# legatus_0_1.net
KiCad netlist of a schematic drawn in EAGLE
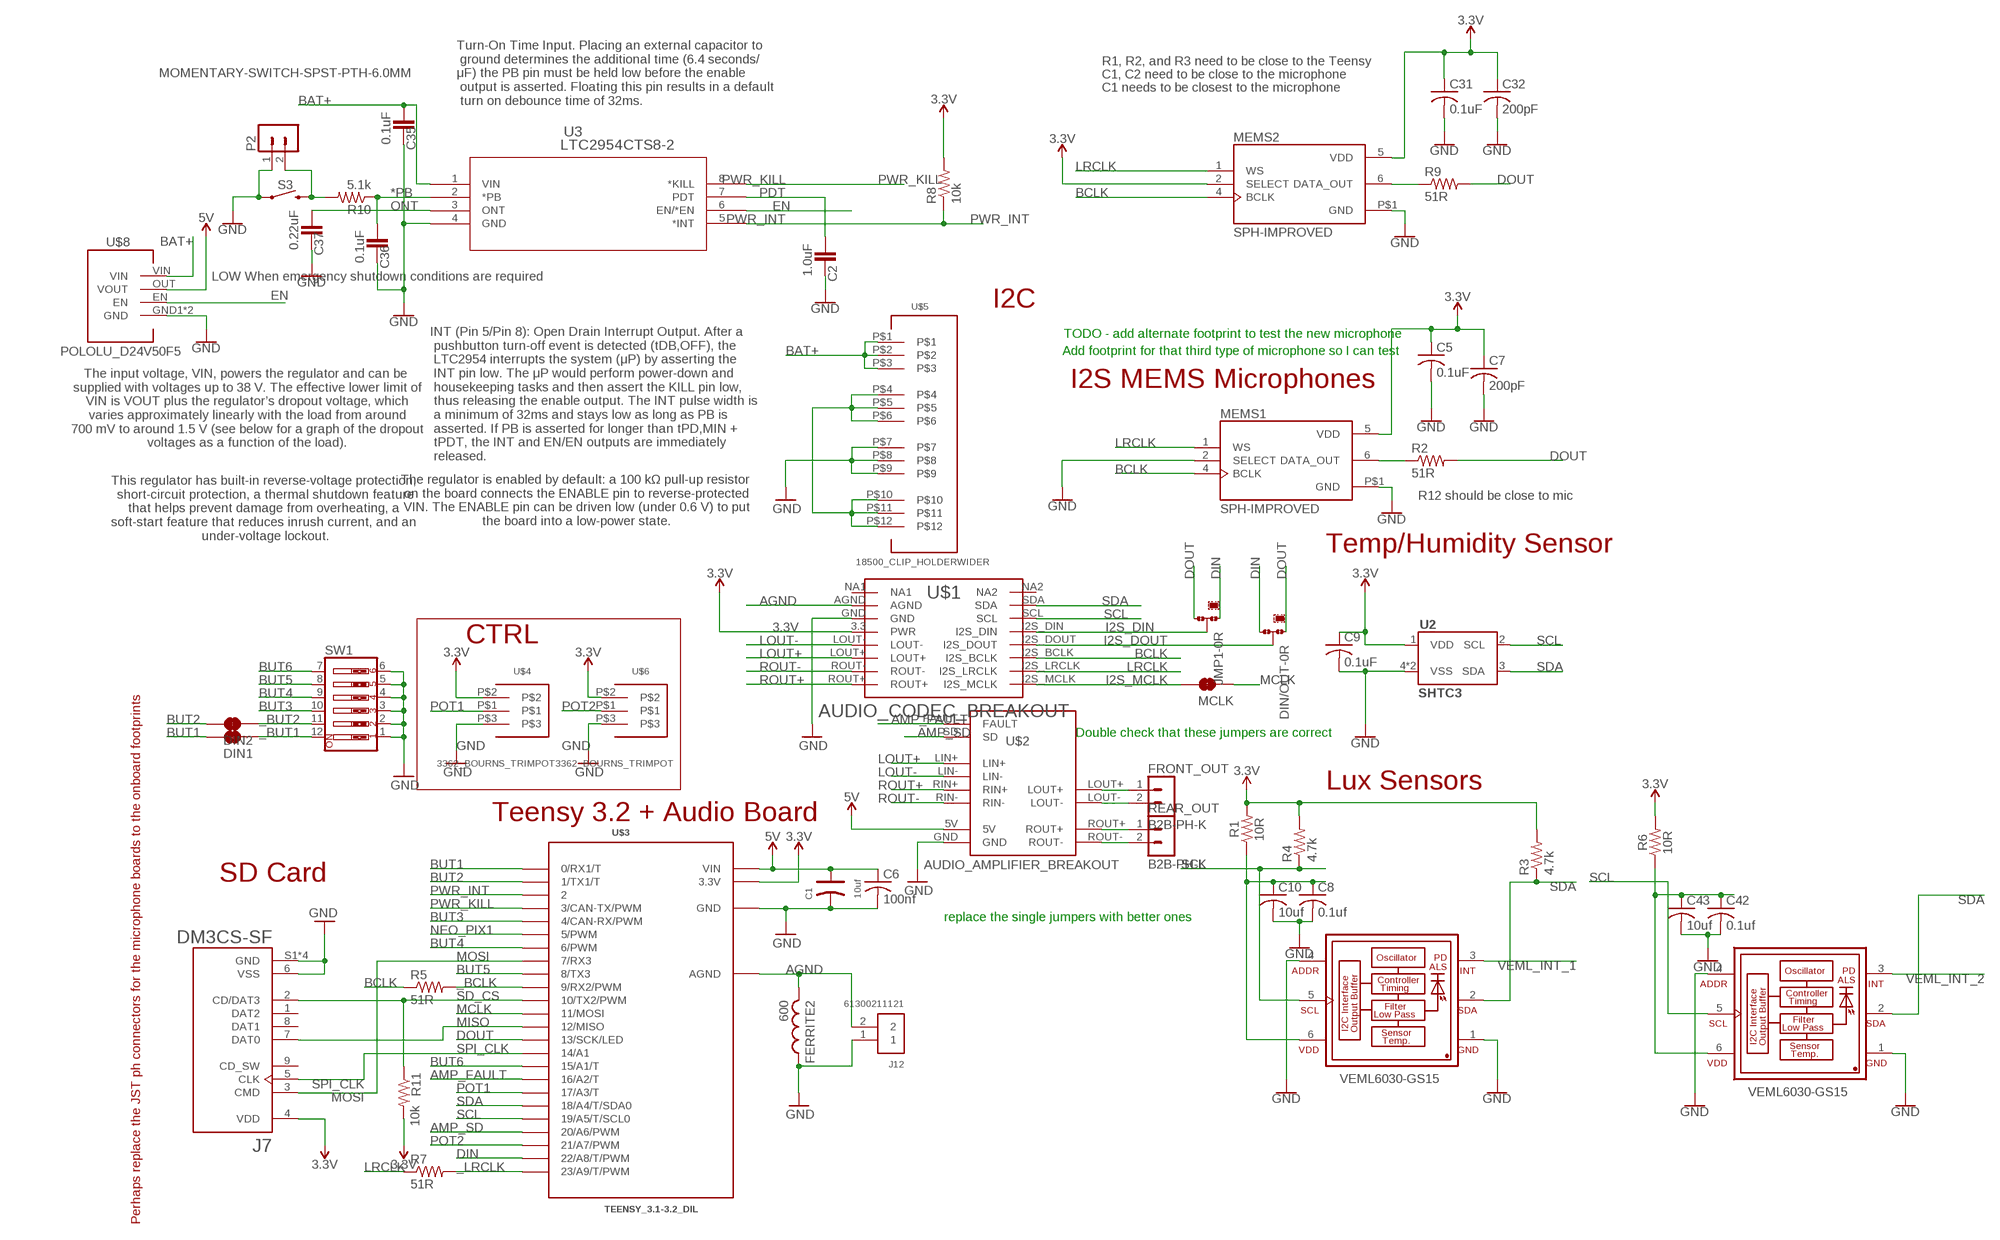
[diagram p0: schematic, sheet 1]
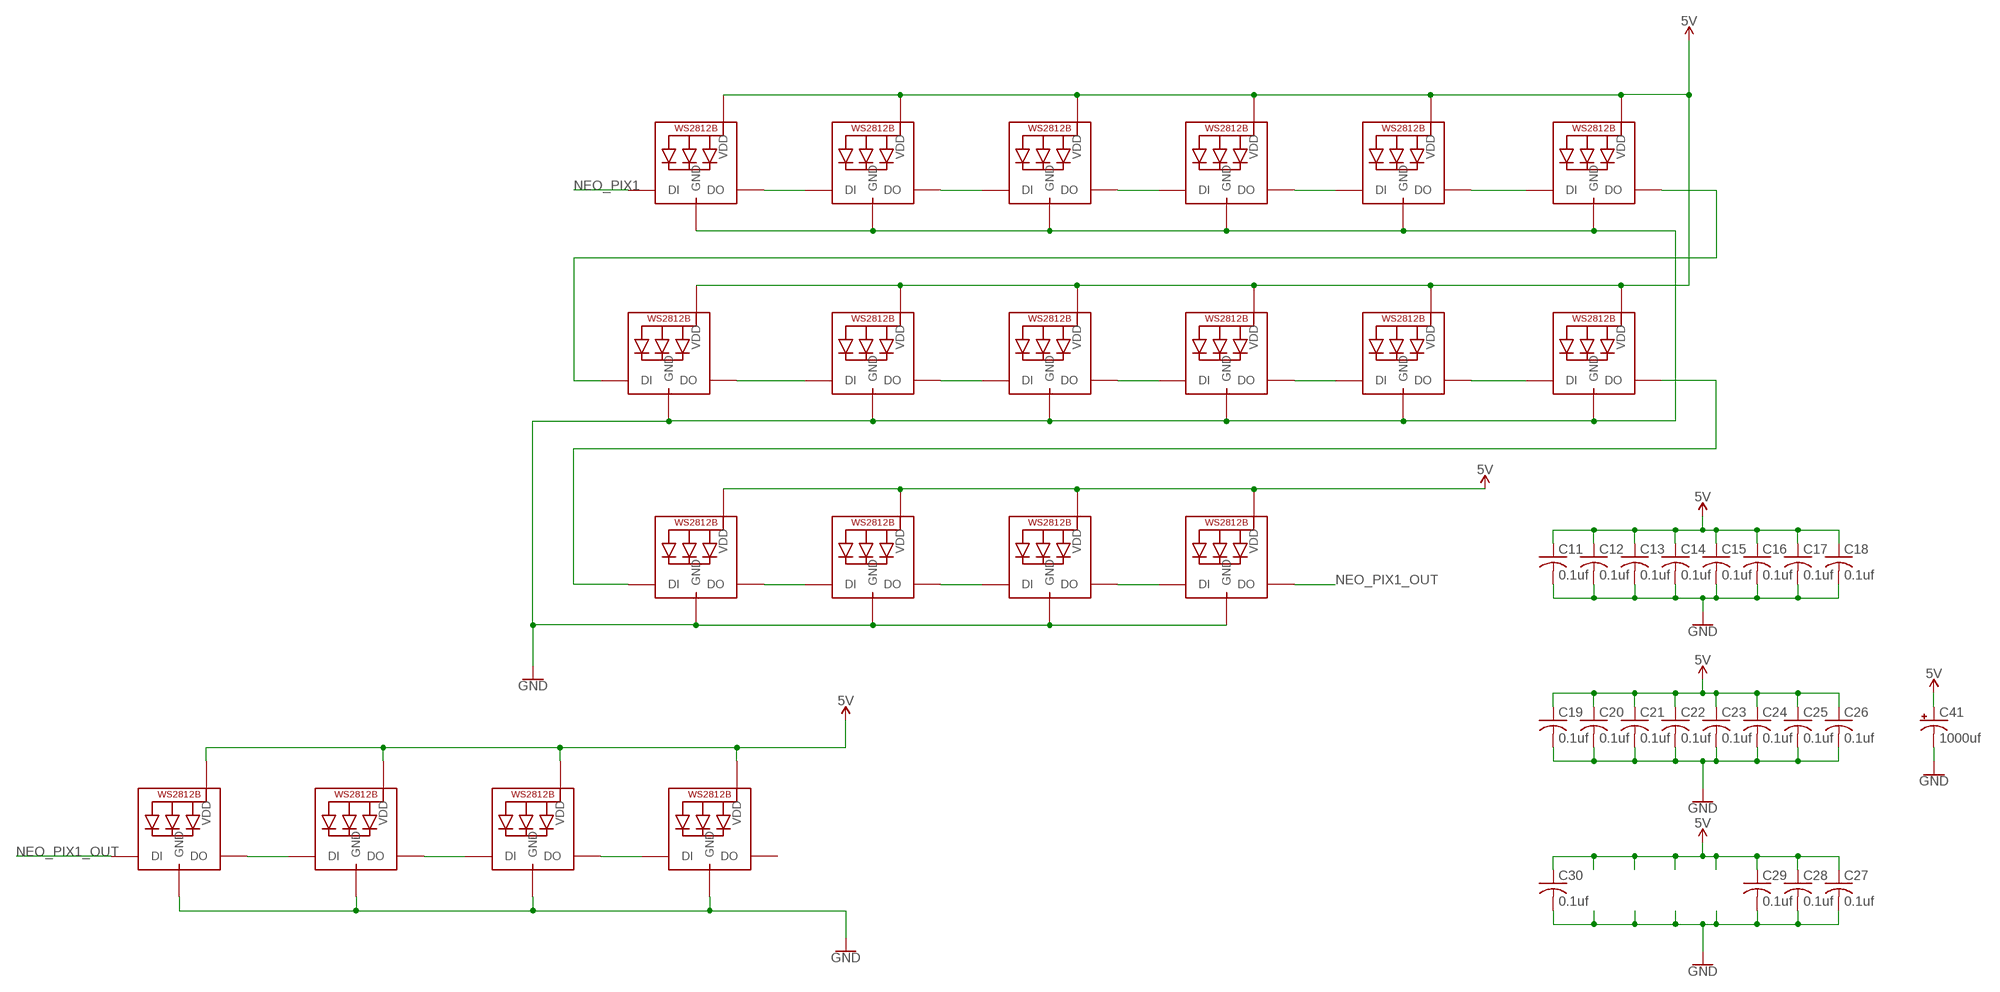
[diagram p1: schematic, sheet 2]

(export (version "E")
  (design (tool "Eeschema 10.0.6"))
  (components
    (comp (ref "C11")
      (value "0.1uf")
      (footprint "eagle-import:C0805")
      (libsource (lib "eagle-import") (part "rcl_334_C-USC0805"))
    )
    (comp (ref "C12")
      (value "0.1uf")
      (footprint "eagle-import:C0805")
      (libsource (lib "eagle-import") (part "rcl_334_C-USC0805"))
    )
    (comp (ref "C13")
      (value "0.1uf")
      (footprint "eagle-import:C0805")
      (libsource (lib "eagle-import") (part "rcl_334_C-USC0805"))
    )
    (comp (ref "C14")
      (value "0.1uf")
      (footprint "eagle-import:C0805")
      (libsource (lib "eagle-import") (part "rcl_334_C-USC0805"))
    )
    (comp (ref "C15")
      (value "0.1uf")
      (footprint "eagle-import:C0805")
      (libsource (lib "eagle-import") (part "rcl_334_C-USC0805"))
    )
    (comp (ref "C16")
      (value "0.1uf")
      (footprint "eagle-import:C0805")
      (libsource (lib "eagle-import") (part "rcl_334_C-USC0805"))
    )
    (comp (ref "C17")
      (value "0.1uf")
      (footprint "eagle-import:C0805")
      (libsource (lib "eagle-import") (part "rcl_334_C-USC0805"))
    )
    (comp (ref "C18")
      (value "0.1uf")
      (footprint "eagle-import:C0805")
      (libsource (lib "eagle-import") (part "rcl_334_C-USC0805"))
    )
    (comp (ref "C19")
      (value "0.1uf")
      (footprint "eagle-import:C0805")
      (libsource (lib "eagle-import") (part "rcl_334_C-USC0805"))
    )
    (comp (ref "C20")
      (value "0.1uf")
      (footprint "eagle-import:C0805")
      (libsource (lib "eagle-import") (part "rcl_334_C-USC0805"))
    )
    (comp (ref "C21")
      (value "0.1uf")
      (footprint "eagle-import:C0805")
      (libsource (lib "eagle-import") (part "rcl_334_C-USC0805"))
    )
    (comp (ref "C22")
      (value "0.1uf")
      (footprint "eagle-import:C0805")
      (libsource (lib "eagle-import") (part "rcl_334_C-USC0805"))
    )
    (comp (ref "C23")
      (value "0.1uf")
      (footprint "eagle-import:C0805")
      (libsource (lib "eagle-import") (part "rcl_334_C-USC0805"))
    )
    (comp (ref "C24")
      (value "0.1uf")
      (footprint "eagle-import:C0805")
      (libsource (lib "eagle-import") (part "rcl_334_C-USC0805"))
    )
    (comp (ref "C25")
      (value "0.1uf")
      (footprint "eagle-import:C0805")
      (libsource (lib "eagle-import") (part "rcl_334_C-USC0805"))
    )
    (comp (ref "C26")
      (value "0.1uf")
      (footprint "eagle-import:C0805")
      (libsource (lib "eagle-import") (part "rcl_334_C-USC0805"))
    )
    (comp (ref "C27")
      (value "0.1uf")
      (footprint "eagle-import:C0805")
      (libsource (lib "eagle-import") (part "rcl_334_C-USC0805"))
    )
    (comp (ref "C28")
      (value "0.1uf")
      (footprint "eagle-import:C0805")
      (libsource (lib "eagle-import") (part "rcl_334_C-USC0805"))
    )
    (comp (ref "C29")
      (value "0.1uf")
      (footprint "eagle-import:C0805")
      (libsource (lib "eagle-import") (part "rcl_334_C-USC0805"))
    )
    (comp (ref "C30")
      (value "0.1uf")
      (footprint "eagle-import:C0805")
      (libsource (lib "eagle-import") (part "rcl_334_C-USC0805"))
    )
    (comp (ref "C41")
      (value "1000uf")
      (footprint "eagle-import:153CLV-1010")
      (libsource (lib "eagle-import") (part "CPOL-US153CLV-1010"))
    )
    (comp (ref "LED1")
      (value "WS2812B_5050N")
      (footprint "eagle-import:WS2812B-NARROW")
      (libsource (lib "eagle-import") (part "WS2812B_5050N"))
    )
    (comp (ref "LED2")
      (value "WS2812B_5050N")
      (footprint "eagle-import:WS2812B-NARROW")
      (libsource (lib "eagle-import") (part "WS2812B_5050N"))
    )
    (comp (ref "LED3")
      (value "WS2812B_5050N")
      (footprint "eagle-import:WS2812B-NARROW")
      (libsource (lib "eagle-import") (part "WS2812B_5050N"))
    )
    (comp (ref "LED4")
      (value "WS2812B_5050N")
      (footprint "eagle-import:WS2812B-NARROW")
      (libsource (lib "eagle-import") (part "WS2812B_5050N"))
    )
    (comp (ref "LED5")
      (value "WS2812B_5050N")
      (footprint "eagle-import:WS2812B-NARROW")
      (libsource (lib "eagle-import") (part "WS2812B_5050N"))
    )
    (comp (ref "LED6")
      (value "WS2812B_5050N")
      (footprint "eagle-import:WS2812B-NARROW")
      (libsource (lib "eagle-import") (part "WS2812B_5050N"))
    )
    (comp (ref "LED7")
      (value "WS2812B_5050N")
      (footprint "eagle-import:WS2812B-NARROW")
      (libsource (lib "eagle-import") (part "WS2812B_5050N"))
    )
    (comp (ref "LED8")
      (value "WS2812B_5050N")
      (footprint "eagle-import:WS2812B-NARROW")
      (libsource (lib "eagle-import") (part "WS2812B_5050N"))
    )
    (comp (ref "LED9")
      (value "WS2812B_5050N")
      (footprint "eagle-import:WS2812B-NARROW")
      (libsource (lib "eagle-import") (part "WS2812B_5050N"))
    )
    (comp (ref "LED10")
      (value "WS2812B_5050N")
      (footprint "eagle-import:WS2812B-NARROW")
      (libsource (lib "eagle-import") (part "WS2812B_5050N"))
    )
    (comp (ref "LED11")
      (value "WS2812B_5050N")
      (footprint "eagle-import:WS2812B-NARROW")
      (libsource (lib "eagle-import") (part "WS2812B_5050N"))
    )
    (comp (ref "LED12")
      (value "WS2812B_5050N")
      (footprint "eagle-import:WS2812B-NARROW")
      (libsource (lib "eagle-import") (part "WS2812B_5050N"))
    )
    (comp (ref "LED13")
      (value "WS2812B_5050N")
      (footprint "eagle-import:WS2812B-NARROW")
      (libsource (lib "eagle-import") (part "WS2812B_5050N"))
    )
    (comp (ref "LED14")
      (value "WS2812B_5050N")
      (footprint "eagle-import:WS2812B-NARROW")
      (libsource (lib "eagle-import") (part "WS2812B_5050N"))
    )
    (comp (ref "LED15")
      (value "WS2812B_5050N")
      (footprint "eagle-import:WS2812B-NARROW")
      (libsource (lib "eagle-import") (part "WS2812B_5050N"))
    )
    (comp (ref "LED16")
      (value "WS2812B_5050N")
      (footprint "eagle-import:WS2812B-NARROW")
      (libsource (lib "eagle-import") (part "WS2812B_5050N"))
    )
    (comp (ref "LED17")
      (value "WS2812B_5050N")
      (footprint "eagle-import:WS2812B-NARROW")
      (libsource (lib "eagle-import") (part "WS2812B_5050N"))
    )
    (comp (ref "LED18")
      (value "WS2812B_5050N")
      (footprint "eagle-import:WS2812B-NARROW")
      (libsource (lib "eagle-import") (part "WS2812B_5050N"))
    )
    (comp (ref "LED19")
      (value "WS2812B_5050N")
      (footprint "eagle-import:WS2812B-NARROW")
      (libsource (lib "eagle-import") (part "WS2812B_5050N"))
    )
    (comp (ref "LED20")
      (value "WS2812B_5050N")
      (footprint "eagle-import:WS2812B-NARROW")
      (libsource (lib "eagle-import") (part "WS2812B_5050N"))
    )
    (comp (ref "C1")
      (value "10uf")
      (footprint "eagle-import:PC-D5.3MM")
      (fields (field (name "MPN") "KS 100uF/16V"))
      (libsource (lib "eagle-import") (part "DIP-ALUMINUM-47UF-16V(D5-H7MM)"))
    )
    (comp (ref "C2")
      (value "1.0uF")
      (footprint "eagle-import:CAPC2012X110")
      (libsource (lib "eagle-import") (part "CCHIP-0805(2012-METRIC)_"))
    )
    (comp (ref "C5")
      (value "0.1uF")
      (footprint "eagle-import:C0805")
      (libsource (lib "eagle-import") (part "rcl_334_C-USC0805"))
    )
    (comp (ref "C6")
      (value "100nf")
      (footprint "eagle-import:C2012")
      (libsource (lib "eagle-import") (part "C-USC2012"))
    )
    (comp (ref "C7")
      (value "200pF")
      (footprint "eagle-import:C0805")
      (libsource (lib "eagle-import") (part "rcl_334_C-USC0805"))
    )
    (comp (ref "C8")
      (value "0.1uf")
      (footprint "eagle-import:C0805")
      (libsource (lib "eagle-import") (part "rcl_334_C-USC0805"))
    )
    (comp (ref "C9")
      (value "0.1uF")
      (footprint "eagle-import:C0805")
      (libsource (lib "eagle-import") (part "rcl_334_C-USC0805"))
    )
    (comp (ref "C10")
      (value "10uf")
      (footprint "eagle-import:C0805")
      (libsource (lib "eagle-import") (part "rcl_334_C-USC0805"))
    )
    (comp (ref "C31")
      (value "0.1uF")
      (footprint "eagle-import:C0805")
      (libsource (lib "eagle-import") (part "rcl_334_C-USC0805"))
    )
    (comp (ref "C32")
      (value "200pF")
      (footprint "eagle-import:C0805")
      (libsource (lib "eagle-import") (part "rcl_334_C-USC0805"))
    )
    (comp (ref "C35")
      (value "0.1uF")
      (footprint "eagle-import:CAPC2012X110")
      (libsource (lib "eagle-import") (part "CCHIP-0805(2012-METRIC)_"))
    )
    (comp (ref "C36")
      (value "0.1uF")
      (footprint "eagle-import:CAPC2012X110")
      (libsource (lib "eagle-import") (part "CCHIP-0805(2012-METRIC)_"))
    )
    (comp (ref "C37")
      (value "0.22uF")
      (footprint "eagle-import:CAPC2012X110")
      (libsource (lib "eagle-import") (part "CCHIP-0805(2012-METRIC)_"))
    )
    (comp (ref "C42")
      (value "0.1uf")
      (footprint "eagle-import:C0805")
      (libsource (lib "eagle-import") (part "rcl_334_C-USC0805"))
    )
    (comp (ref "C43")
      (value "10uf")
      (footprint "eagle-import:C0805")
      (libsource (lib "eagle-import") (part "rcl_334_C-USC0805"))
    )
    (comp (ref "DIN/OUT")
      (value "0R-JUMPB")
      (footprint "eagle-import:B0R-JMP")
      (libsource (lib "eagle-import") (part "0R-JUMPB"))
    )
    (comp (ref "DIN1")
      (value "JUMPER-SMT_2_NC_TRACE_SILK")
      (footprint "eagle-import:SMT-JUMPER_2_NC_TRACE_SILK")
      (libsource (lib "eagle-import") (part "JUMPER-SMT_2_NC_TRACE_SILK"))
    )
    (comp (ref "DIN2")
      (value "JUMPER-SMT_2_NC_TRACE_SILK")
      (footprint "eagle-import:SMT-JUMPER_2_NC_TRACE_SILK")
      (libsource (lib "eagle-import") (part "JUMPER-SMT_2_NC_TRACE_SILK"))
    )
    (comp (ref "FERRITE2")
      (value "600")
      (footprint "eagle-import:RESC0805_N")
      (libsource (lib "eagle-import") (part "INDUCTOR_0805_N"))
    )
    (comp (ref "FRONT_OUT")
      (value "B2B-PH-K")
      (footprint "eagle-import:B2B-PH-K")
      (libsource (lib "eagle-import") (part "B2B-PH-K"))
    )
    (comp (ref "J7")
      (value "DM3CS-SF")
      (footprint "eagle-import:HRS_DM3CS-SF")
      (fields (field (name "MF") "Hirose"))
      (libsource (lib "eagle-import") (part "DM3CS-SF"))
    )
    (comp (ref "J12")
      (value "61300211121")
      (footprint "eagle-import:61300211121")
      (fields
        (field (name "DIGI_KEY_PART_NUMBER") "732-5315-ND")
        (field (name "MANUFACTURER") "Wurth Electronics Inc.")
        (field (name "CREATED_BY") "PCBLayout.com")
      )
      (libsource (lib "eagle-import") (part "61300211121"))
    )
    (comp (ref "JMP1")
      (value "0R-JUMPB")
      (footprint "eagle-import:B0R-JMP")
      (libsource (lib "eagle-import") (part "0R-JUMPB"))
    )
    (comp (ref "MCLK")
      (value "JUMPER-SMT_2_NC_TRACE_SILK")
      (footprint "eagle-import:SMT-JUMPER_2_NC_TRACE_SILK")
      (libsource (lib "eagle-import") (part "JUMPER-SMT_2_NC_TRACE_SILK"))
    )
    (comp (ref "MEMS1")
      (value "SPH-IMPROVED")
      (footprint "eagle-import:MIC_SPH0645LM4H-B_LARGER_RING")
      (libsource (lib "eagle-import") (part "SPH-IMPROVED"))
    )
    (comp (ref "MEMS2")
      (value "SPH-IMPROVED")
      (footprint "eagle-import:MIC_SPH0645LM4H-B_LARGER_RING")
      (libsource (lib "eagle-import") (part "SPH-IMPROVED"))
    )
    (comp (ref "P2")
      (value "B2B-PH-K")
      (footprint "eagle-import:B2B-PH-K")
      (libsource (lib "eagle-import") (part "B2B-PH-K"))
    )
    (comp (ref "R1")
      (value "10R")
      (footprint "eagle-import:R0805")
      (libsource (lib "eagle-import") (part "audio amplifier example_970892_R-US_R0805"))
    )
    (comp (ref "R2")
      (value "51R")
      (footprint "eagle-import:M0805")
      (libsource (lib "eagle-import") (part "adafruit_420_R-US_M0805"))
    )
    (comp (ref "R3")
      (value "4.7k")
      (footprint "eagle-import:M0805")
      (libsource (lib "eagle-import") (part "adafruit_420_R-US_M0805"))
    )
    (comp (ref "R4")
      (value "4.7k")
      (footprint "eagle-import:M0805")
      (libsource (lib "eagle-import") (part "adafruit_420_R-US_M0805"))
    )
    (comp (ref "R5")
      (value "51R")
      (footprint "eagle-import:M0805")
      (libsource (lib "eagle-import") (part "adafruit_420_R-US_M0805"))
    )
    (comp (ref "R6")
      (value "10R")
      (footprint "eagle-import:R0805")
      (libsource (lib "eagle-import") (part "audio amplifier example_970892_R-US_R0805"))
    )
    (comp (ref "R7")
      (value "51R")
      (footprint "eagle-import:M0805")
      (libsource (lib "eagle-import") (part "adafruit_420_R-US_M0805"))
    )
    (comp (ref "R8")
      (value "10k")
      (footprint "eagle-import:R0805")
      (libsource (lib "eagle-import") (part "R-US_R0805"))
    )
    (comp (ref "R9")
      (value "51R")
      (footprint "eagle-import:M0805")
      (libsource (lib "eagle-import") (part "adafruit_420_R-US_M0805"))
    )
    (comp (ref "R10")
      (value "5.1k")
      (footprint "eagle-import:R0805")
      (libsource (lib "eagle-import") (part "R-US_R0805"))
    )
    (comp (ref "R11")
      (value "10k")
      (footprint "eagle-import:M0805")
      (libsource (lib "eagle-import") (part "rcl_R-US_M0805"))
    )
    (comp (ref "REAR_OUT")
      (value "B2B-PH-K")
      (footprint "eagle-import:B2B-PH-K")
      (libsource (lib "eagle-import") (part "B2B-PH-K"))
    )
    (comp (ref "S3")
      (value "MOMENTARY-SWITCH-SPST-PTH-6.0MM")
      (footprint "eagle-import:TACTILE_SWITCH_PTH_6.0MM")
      (libsource (lib "eagle-import") (part "MOMENTARY-SWITCH-SPST-PTH-6.0MM"))
    )
    (comp (ref "SW1")
      (value "SW_DIP-6")
      (footprint "eagle-import:EDG-06")
      (libsource (lib "eagle-import") (part "SW_DIP-6"))
    )
    (comp (ref "U$1")
      (value "AUDIO_CODEC_BREAKOUT")
      (footprint "eagle-import:HSS_CODEC_BREAKOUT")
      (libsource (lib "eagle-import") (part "AUDIO_CODEC_BREAKOUT"))
    )
    (comp (ref "U$2")
      (value "AUDIO_AMPLIFIER_BREAKOUT")
      (footprint "eagle-import:AUDIO_AMPLIFIER_BREAKOUT")
      (libsource (lib "eagle-import") (part "AUDIO_AMPLIFIER_BREAKOUT"))
    )
    (comp (ref "U$3")
      (value "TEENSY_3.1-3.2_DIL")
      (footprint "eagle-import:TEENSY_3.0-3.2&LC_DIL")
      (libsource (lib "eagle-import") (part "TEENSY_3.1-3.2_DIL"))
    )
    (comp (ref "U$4")
      (value "3362_BOURNS_TRIMPOT")
      (footprint "eagle-import:3362_BOURNS_TRIMPOT")
      (libsource (lib "eagle-import") (part "3362_BOURNS_TRIMPOT"))
    )
    (comp (ref "U$5")
      (value "18500_CLIP_HOLDERWIDER")
      (footprint "eagle-import:3PINBATTERY_CLIP_WIDER")
      (libsource (lib "eagle-import") (part "18500_CLIP_HOLDERWIDER"))
    )
    (comp (ref "U$6")
      (value "3362_BOURNS_TRIMPOT")
      (footprint "eagle-import:3362_BOURNS_TRIMPOT")
      (libsource (lib "eagle-import") (part "3362_BOURNS_TRIMPOT"))
    )
    (comp (ref "U$8")
      (value "POLOLU_D24V50F5")
      (footprint "eagle-import:POLOLU_D24V50F5")
      (libsource (lib "eagle-import") (part "POLOLU_D24V50F5"))
    )
    (comp (ref "U2")
      (value "SHTC3")
      (footprint "eagle-import:SHTC3")
      (libsource (lib "eagle-import") (part "SHTC3"))
    )
    (comp (ref "U3")
      (value "LTC2954CTS8-2")
      (footprint "eagle-import:TSOT-23_TS8")
      (fields (field (name "MF") "Analog Devices / Linear Technology"))
      (libsource (lib "eagle-import") (part "LTC2954CTS8-2"))
    )
    (comp (ref "VMEL1")
      (value "VEML6030-GS15")
      (footprint "eagle-import:VISHAY_VEML6030_2X2X0.87")
      (fields (field (name "MF") "Vishay Semiconductor"))
      (libsource (lib "eagle-import") (part "VEML6030-GS15"))
    )
    (comp (ref "VMEL2")
      (value "VEML6030-GS15")
      (footprint "eagle-import:VISHAY_VEML6030_2X2X0.87")
      (fields (field (name "MF") "Vishay Semiconductor"))
      (libsource (lib "eagle-import") (part "VEML6030-GS15"))
    )
  )
  (nets
    (net (code "1") (name "*PB") (class "Default")
      (node (ref "P2") (pin "2") (pinfunction "2_2") (pintype "passive"))
      (node (ref "R10") (pin "2") (pinfunction "2_2") (pintype "passive"))
      (node (ref "S3") (pin "3") (pinfunction "2_3") (pintype "passive"))
    )
    (net (code "2") (name "3.3V") (class "Default")
      (node (ref "C31") (pin "1") (pinfunction "1_1") (pintype "passive"))
      (node (ref "C32") (pin "1") (pinfunction "1_1") (pintype "passive"))
      (node (ref "C5") (pin "1") (pinfunction "1_1") (pintype "passive"))
      (node (ref "C7") (pin "1") (pinfunction "1_1") (pintype "passive"))
      (node (ref "C9") (pin "1") (pinfunction "1_1") (pintype "passive"))
      (node (ref "J7") (pin "4") (pinfunction "VDD_4") (pintype "passive"))
      (node (ref "MEMS1") (pin "5") (pinfunction "VDD_5") (pintype "power_in"))
      (node (ref "MEMS2") (pin "2") (pinfunction "SELECT_2") (pintype "input"))
      (node (ref "MEMS2") (pin "5") (pinfunction "VDD_5") (pintype "power_in"))
      (node (ref "R1") (pin "2") (pinfunction "2_2") (pintype "passive"))
      (node (ref "R11") (pin "2") (pinfunction "2_2") (pintype "passive"))
      (node (ref "R3") (pin "2") (pinfunction "2_2") (pintype "passive"))
      (node (ref "R4") (pin "2") (pinfunction "2_2") (pintype "passive"))
      (node (ref "R6") (pin "2") (pinfunction "2_2") (pintype "passive"))
      (node (ref "R8") (pin "2") (pinfunction "2_2") (pintype "passive"))
      (node (ref "U$1") (pin "3.3") (pinfunction "PWR_3.3") (pintype "bidirectional"))
      (node (ref "U$3") (pin "3.3V") (pinfunction "3.3V_3.3V") (pintype "power_in"))
      (node (ref "U$4") (pin "P$2") (pinfunction "P$2_P$2") (pintype "bidirectional"))
      (node (ref "U$6") (pin "P$2") (pinfunction "P$2_P$2") (pintype "bidirectional"))
      (node (ref "U2") (pin "1") (pinfunction "VDD_1") (pintype "bidirectional"))
    )
    (net (code "3") (name "5V") (class "Default")
      (node (ref "C1") (pin "+") (pinfunction "+_+") (pintype "passive"))
      (node (ref "C11") (pin "1") (pinfunction "1_1") (pintype "passive"))
      (node (ref "C12") (pin "1") (pinfunction "1_1") (pintype "passive"))
      (node (ref "C13") (pin "1") (pinfunction "1_1") (pintype "passive"))
      (node (ref "C14") (pin "1") (pinfunction "1_1") (pintype "passive"))
      (node (ref "C15") (pin "1") (pinfunction "1_1") (pintype "passive"))
      (node (ref "C16") (pin "1") (pinfunction "1_1") (pintype "passive"))
      (node (ref "C17") (pin "1") (pinfunction "1_1") (pintype "passive"))
      (node (ref "C18") (pin "1") (pinfunction "1_1") (pintype "passive"))
      (node (ref "C19") (pin "1") (pinfunction "1_1") (pintype "passive"))
      (node (ref "C20") (pin "1") (pinfunction "1_1") (pintype "passive"))
      (node (ref "C21") (pin "1") (pinfunction "1_1") (pintype "passive"))
      (node (ref "C22") (pin "1") (pinfunction "1_1") (pintype "passive"))
      (node (ref "C23") (pin "1") (pinfunction "1_1") (pintype "passive"))
      (node (ref "C24") (pin "1") (pinfunction "1_1") (pintype "passive"))
      (node (ref "C25") (pin "1") (pinfunction "1_1") (pintype "passive"))
      (node (ref "C26") (pin "1") (pinfunction "1_1") (pintype "passive"))
      (node (ref "C27") (pin "1") (pinfunction "1_1") (pintype "passive"))
      (node (ref "C28") (pin "1") (pinfunction "1_1") (pintype "passive"))
      (node (ref "C29") (pin "1") (pinfunction "1_1") (pintype "passive"))
      (node (ref "C30") (pin "1") (pinfunction "1_1") (pintype "passive"))
      (node (ref "C41") (pin "+") (pinfunction "+_+") (pintype "passive"))
      (node (ref "C6") (pin "1") (pinfunction "1_1") (pintype "passive"))
      (node (ref "LED1") (pin "1-VDD") (pinfunction "VDD_1-VDD") (pintype "power_in"))
      (node (ref "LED10") (pin "1-VDD") (pinfunction "VDD_1-VDD") (pintype "power_in"))
      (node (ref "LED11") (pin "1-VDD") (pinfunction "VDD_1-VDD") (pintype "power_in"))
      (node (ref "LED12") (pin "1-VDD") (pinfunction "VDD_1-VDD") (pintype "power_in"))
      (node (ref "LED13") (pin "1-VDD") (pinfunction "VDD_1-VDD") (pintype "power_in"))
      (node (ref "LED14") (pin "1-VDD") (pinfunction "VDD_1-VDD") (pintype "power_in"))
      (node (ref "LED15") (pin "1-VDD") (pinfunction "VDD_1-VDD") (pintype "power_in"))
      (node (ref "LED16") (pin "1-VDD") (pinfunction "VDD_1-VDD") (pintype "power_in"))
      (node (ref "LED17") (pin "1-VDD") (pinfunction "VDD_1-VDD") (pintype "power_in"))
      (node (ref "LED18") (pin "1-VDD") (pinfunction "VDD_1-VDD") (pintype "power_in"))
      (node (ref "LED19") (pin "1-VDD") (pinfunction "VDD_1-VDD") (pintype "power_in"))
      (node (ref "LED2") (pin "1-VDD") (pinfunction "VDD_1-VDD") (pintype "power_in"))
      (node (ref "LED20") (pin "1-VDD") (pinfunction "VDD_1-VDD") (pintype "power_in"))
      (node (ref "LED3") (pin "1-VDD") (pinfunction "VDD_1-VDD") (pintype "power_in"))
      (node (ref "LED4") (pin "1-VDD") (pinfunction "VDD_1-VDD") (pintype "power_in"))
      (node (ref "LED5") (pin "1-VDD") (pinfunction "VDD_1-VDD") (pintype "power_in"))
      (node (ref "LED6") (pin "1-VDD") (pinfunction "VDD_1-VDD") (pintype "power_in"))
      (node (ref "LED7") (pin "1-VDD") (pinfunction "VDD_1-VDD") (pintype "power_in"))
      (node (ref "LED8") (pin "1-VDD") (pinfunction "VDD_1-VDD") (pintype "power_in"))
      (node (ref "LED9") (pin "1-VDD") (pinfunction "VDD_1-VDD") (pintype "power_in"))
      (node (ref "U$2") (pin "5V") (pinfunction "5V_5V") (pintype "bidirectional"))
      (node (ref "U$3") (pin "VIN") (pinfunction "VIN_VIN") (pintype "power_in"))
      (node (ref "U$8") (pin "OUT") (pinfunction "VOUT_OUT") (pintype "bidirectional"))
    )
    (net (code "4") (name "AGND") (class "Default")
      (node (ref "FERRITE2") (pin "2") (pinfunction "2_2") (pintype "passive"))
      (node (ref "J12") (pin "2") (pinfunction "2_2") (pintype "passive"))
      (node (ref "U$1") (pin "AGND") (pinfunction "AGND_AGND") (pintype "bidirectional"))
      (node (ref "U$3") (pin "AGND") (pinfunction "AGND_AGND") (pintype "power_in"))
    )
    (net (code "5") (name "AMP_FAULT") (class "Default")
      (node (ref "U$2") (pin "FAULT") (pinfunction "FAULT_FAULT") (pintype "bidirectional"))
      (node (ref "U$3") (pin "16/A2") (pinfunction "16/A2/T_16/A2") (pintype "bidirectional"))
    )
    (net (code "6") (name "AMP_SD") (class "Default")
      (node (ref "U$2") (pin "SD") (pinfunction "SD_SD") (pintype "bidirectional"))
      (node (ref "U$3") (pin "20/A6") (pinfunction "20/A6/PWM_20/A6") (pintype "bidirectional"))
    )
    (net (code "7") (name "BAT+") (class "Default")
      (node (ref "C35") (pin "1") (pinfunction "1_1") (pintype "passive"))
      (node (ref "U$5") (pin "P$1") (pinfunction "P$1_P$1") (pintype "bidirectional"))
      (node (ref "U$5") (pin "P$2") (pinfunction "P$2_P$2") (pintype "bidirectional"))
      (node (ref "U$5") (pin "P$3") (pinfunction "P$3_P$3") (pintype "bidirectional"))
      (node (ref "U$8") (pin "VIN") (pinfunction "VIN_VIN") (pintype "bidirectional"))
      (node (ref "U3") (pin "1") (pinfunction "VIN_1") (pintype "input"))
    )
    (net (code "8") (name "BCLK") (class "Default")
      (node (ref "MEMS1") (pin "4") (pinfunction "BCLK_4") (pintype "input"))
      (node (ref "MEMS2") (pin "4") (pinfunction "BCLK_4") (pintype "input"))
      (node (ref "R5") (pin "1") (pinfunction "1_1") (pintype "passive"))
      (node (ref "U$1") (pin "I2S_BCLK") (pinfunction "I2S_BCLK_I2S_BCLK") (pintype "bidirectional"))
    )
    (net (code "9") (name "BUT1") (class "Default")
      (node (ref "DIN1") (pin "1") (pinfunction "1_1") (pintype "passive"))
      (node (ref "U$3") (pin "0") (pinfunction "0/RX1/T_0") (pintype "bidirectional"))
    )
    (net (code "10") (name "BUT2") (class "Default")
      (node (ref "DIN2") (pin "1") (pinfunction "1_1") (pintype "passive"))
      (node (ref "U$3") (pin "1") (pinfunction "1/TX1/T_1") (pintype "bidirectional"))
    )
    (net (code "11") (name "BUT3") (class "Default")
      (node (ref "SW1") (pin "10") (pinfunction "10_10") (pintype "passive"))
      (node (ref "U$3") (pin "4") (pinfunction "4/CAN-RX/PWM_4") (pintype "bidirectional"))
    )
    (net (code "12") (name "BUT4") (class "Default")
      (node (ref "SW1") (pin "9") (pinfunction "9_9") (pintype "passive"))
      (node (ref "U$3") (pin "6") (pinfunction "6/PWM_6") (pintype "bidirectional"))
    )
    (net (code "13") (name "BUT5") (class "Default")
      (node (ref "SW1") (pin "8") (pinfunction "8_8") (pintype "passive"))
      (node (ref "U$3") (pin "8") (pinfunction "8/TX3_8") (pintype "bidirectional"))
    )
    (net (code "14") (name "BUT6") (class "Default")
      (node (ref "SW1") (pin "7") (pinfunction "7_7") (pintype "passive"))
      (node (ref "U$3") (pin "15/A1") (pinfunction "15/A1/T_15/A1") (pintype "bidirectional"))
    )
    (net (code "15") (name "DIN") (class "Default")
      (node (ref "DIN/OUT") (pin "3") (pinfunction "3_3") (pintype "passive"))
      (node (ref "JMP1") (pin "1") (pinfunction "1_1") (pintype "passive"))
      (node (ref "U$3") (pin "22/A8") (pinfunction "22/A8/T/PWM_22/A8") (pintype "bidirectional"))
    )
    (net (code "16") (name "DOUT") (class "Default")
      (node (ref "DIN/OUT") (pin "1") (pinfunction "1_1") (pintype "passive"))
      (node (ref "JMP1") (pin "3") (pinfunction "3_3") (pintype "passive"))
      (node (ref "R2") (pin "2") (pinfunction "2_2") (pintype "passive"))
      (node (ref "R9") (pin "2") (pinfunction "2_2") (pintype "passive"))
      (node (ref "U$3") (pin "13") (pinfunction "13/SCK/LED_13") (pintype "bidirectional"))
    )
    (net (code "17") (name "EN") (class "Default")
      (node (ref "U$8") (pin "EN") (pinfunction "EN_EN") (pintype "bidirectional"))
      (node (ref "U3") (pin "6") (pinfunction "EN/*EN_6") (pintype "output"))
    )
    (net (code "18") (name "GND") (class "Default")
      (node (ref "C1") (pin "-") (pinfunction "-_-") (pintype "passive"))
      (node (ref "C10") (pin "2") (pinfunction "2_2") (pintype "passive"))
      (node (ref "C11") (pin "2") (pinfunction "2_2") (pintype "passive"))
      (node (ref "C12") (pin "2") (pinfunction "2_2") (pintype "passive"))
      (node (ref "C13") (pin "2") (pinfunction "2_2") (pintype "passive"))
      (node (ref "C14") (pin "2") (pinfunction "2_2") (pintype "passive"))
      (node (ref "C15") (pin "2") (pinfunction "2_2") (pintype "passive"))
      (node (ref "C16") (pin "2") (pinfunction "2_2") (pintype "passive"))
      (node (ref "C17") (pin "2") (pinfunction "2_2") (pintype "passive"))
      (node (ref "C18") (pin "2") (pinfunction "2_2") (pintype "passive"))
      (node (ref "C19") (pin "2") (pinfunction "2_2") (pintype "passive"))
      (node (ref "C2") (pin "2") (pinfunction "2_2") (pintype "passive"))
      (node (ref "C20") (pin "2") (pinfunction "2_2") (pintype "passive"))
      (node (ref "C21") (pin "2") (pinfunction "2_2") (pintype "passive"))
      (node (ref "C22") (pin "2") (pinfunction "2_2") (pintype "passive"))
      (node (ref "C23") (pin "2") (pinfunction "2_2") (pintype "passive"))
      (node (ref "C24") (pin "2") (pinfunction "2_2") (pintype "passive"))
      (node (ref "C25") (pin "2") (pinfunction "2_2") (pintype "passive"))
      (node (ref "C26") (pin "2") (pinfunction "2_2") (pintype "passive"))
      (node (ref "C27") (pin "2") (pinfunction "2_2") (pintype "passive"))
      (node (ref "C28") (pin "2") (pinfunction "2_2") (pintype "passive"))
      (node (ref "C29") (pin "2") (pinfunction "2_2") (pintype "passive"))
      (node (ref "C30") (pin "2") (pinfunction "2_2") (pintype "passive"))
      (node (ref "C31") (pin "2") (pinfunction "2_2") (pintype "passive"))
      (node (ref "C32") (pin "2") (pinfunction "2_2") (pintype "passive"))
      (node (ref "C35") (pin "2") (pinfunction "2_2") (pintype "passive"))
      (node (ref "C36") (pin "2") (pinfunction "2_2") (pintype "passive"))
      (node (ref "C37") (pin "2") (pinfunction "2_2") (pintype "passive"))
      (node (ref "C41") (pin "-") (pinfunction "-_-") (pintype "passive"))
      (node (ref "C42") (pin "2") (pinfunction "2_2") (pintype "passive"))
      (node (ref "C43") (pin "2") (pinfunction "2_2") (pintype "passive"))
      (node (ref "C5") (pin "2") (pinfunction "2_2") (pintype "passive"))
      (node (ref "C6") (pin "2") (pinfunction "2_2") (pintype "passive"))
      (node (ref "C7") (pin "2") (pinfunction "2_2") (pintype "passive"))
      (node (ref "C8") (pin "2") (pinfunction "2_2") (pintype "passive"))
      (node (ref "C9") (pin "2") (pinfunction "2_2") (pintype "passive"))
      (node (ref "FERRITE2") (pin "1") (pinfunction "1_1") (pintype "passive"))
      (node (ref "J12") (pin "1") (pinfunction "1_1") (pintype "passive"))
      (node (ref "J7") (pin "6") (pinfunction "VSS_6") (pintype "passive"))
      (node (ref "J7") (pin "S1") (pinfunction "GND_S1") (pintype "passive"))
      (node (ref "J7") (pin "S2") (pinfunction "GND_S2") (pintype "passive"))
      (node (ref "J7") (pin "S3") (pinfunction "GND_S3") (pintype "passive"))
      (node (ref "J7") (pin "S5") (pinfunction "GND_S5") (pintype "passive"))
      (node (ref "LED1") (pin "3-GND") (pinfunction "GND_3-GND") (pintype "power_in"))
      (node (ref "LED10") (pin "3-GND") (pinfunction "GND_3-GND") (pintype "power_in"))
      (node (ref "LED11") (pin "3-GND") (pinfunction "GND_3-GND") (pintype "power_in"))
      (node (ref "LED12") (pin "3-GND") (pinfunction "GND_3-GND") (pintype "power_in"))
      (node (ref "LED13") (pin "3-GND") (pinfunction "GND_3-GND") (pintype "power_in"))
      (node (ref "LED14") (pin "3-GND") (pinfunction "GND_3-GND") (pintype "power_in"))
      (node (ref "LED15") (pin "3-GND") (pinfunction "GND_3-GND") (pintype "power_in"))
      (node (ref "LED16") (pin "3-GND") (pinfunction "GND_3-GND") (pintype "power_in"))
      (node (ref "LED17") (pin "3-GND") (pinfunction "GND_3-GND") (pintype "power_in"))
      (node (ref "LED18") (pin "3-GND") (pinfunction "GND_3-GND") (pintype "power_in"))
      (node (ref "LED19") (pin "3-GND") (pinfunction "GND_3-GND") (pintype "power_in"))
      (node (ref "LED2") (pin "3-GND") (pinfunction "GND_3-GND") (pintype "power_in"))
      (node (ref "LED20") (pin "3-GND") (pinfunction "GND_3-GND") (pintype "power_in"))
      (node (ref "LED3") (pin "3-GND") (pinfunction "GND_3-GND") (pintype "power_in"))
      (node (ref "LED4") (pin "3-GND") (pinfunction "GND_3-GND") (pintype "power_in"))
      (node (ref "LED5") (pin "3-GND") (pinfunction "GND_3-GND") (pintype "power_in"))
      (node (ref "LED6") (pin "3-GND") (pinfunction "GND_3-GND") (pintype "power_in"))
      (node (ref "LED7") (pin "3-GND") (pinfunction "GND_3-GND") (pintype "power_in"))
      (node (ref "LED8") (pin "3-GND") (pinfunction "GND_3-GND") (pintype "power_in"))
      (node (ref "LED9") (pin "3-GND") (pinfunction "GND_3-GND") (pintype "power_in"))
      (node (ref "MEMS1") (pin "2") (pinfunction "SELECT_2") (pintype "input"))
      (node (ref "MEMS1") (pin "P$1") (pinfunction "GND_P$1") (pintype "power_in"))
      (node (ref "MEMS2") (pin "P$1") (pinfunction "GND_P$1") (pintype "power_in"))
      (node (ref "P2") (pin "1") (pinfunction "1_1") (pintype "passive"))
      (node (ref "S3") (pin "1") (pinfunction "1_1") (pintype "passive"))
      (node (ref "SW1") (pin "1") (pinfunction "1_1") (pintype "passive"))
      (node (ref "SW1") (pin "2") (pinfunction "2_2") (pintype "passive"))
      (node (ref "SW1") (pin "3") (pinfunction "3_3") (pintype "passive"))
      (node (ref "SW1") (pin "4") (pinfunction "4_4") (pintype "passive"))
      (node (ref "SW1") (pin "5") (pinfunction "5_5") (pintype "passive"))
      (node (ref "SW1") (pin "6") (pinfunction "6_6") (pintype "passive"))
      (node (ref "U$1") (pin "GND") (pinfunction "GND_GND") (pintype "bidirectional"))
      (node (ref "U$2") (pin "GND") (pinfunction "GND_GND") (pintype "bidirectional"))
      (node (ref "U$3") (pin "GND") (pinfunction "GND_GND") (pintype "power_in"))
      (node (ref "U$4") (pin "P$3") (pinfunction "P$3_P$3") (pintype "bidirectional"))
      (node (ref "U$5") (pin "P$7") (pinfunction "P$7_P$7") (pintype "bidirectional"))
      (node (ref "U$5") (pin "P$8") (pinfunction "P$8_P$8") (pintype "bidirectional"))
      (node (ref "U$5") (pin "P$9") (pinfunction "P$9_P$9") (pintype "bidirectional"))
      (node (ref "U$6") (pin "P$3") (pinfunction "P$3_P$3") (pintype "bidirectional"))
      (node (ref "U$8") (pin "GND1") (pinfunction "GND_GND1") (pintype "bidirectional"))
      (node (ref "U$8") (pin "GND2") (pinfunction "GND_GND2") (pintype "bidirectional"))
      (node (ref "U2") (pin "4") (pinfunction "VSS_4") (pintype "bidirectional"))
      (node (ref "U2") (pin "5") (pinfunction "VSS_5") (pintype "bidirectional"))
      (node (ref "U3") (pin "4") (pinfunction "GND_4") (pintype "power_in"))
      (node (ref "VMEL1") (pin "1") (pinfunction "GND_1") (pintype "power_in"))
      (node (ref "VMEL1") (pin "4") (pinfunction "ADDR_4") (pintype "bidirectional"))
      (node (ref "VMEL2") (pin "1") (pinfunction "GND_1") (pintype "power_in"))
      (node (ref "VMEL2") (pin "4") (pinfunction "ADDR_4") (pintype "bidirectional"))
    )
    (net (code "19") (name "I2S_DIN") (class "Default")
      (node (ref "JMP1") (pin "2") (pinfunction "2_2") (pintype "passive"))
      (node (ref "U$1") (pin "I2S_DIN") (pinfunction "I2S_DIN_I2S_DIN") (pintype "bidirectional"))
    )
    (net (code "20") (name "I2S_DOUT") (class "Default")
      (node (ref "DIN/OUT") (pin "2") (pinfunction "2_2") (pintype "passive"))
      (node (ref "U$1") (pin "I2S_DOUT") (pinfunction "I2S_DOUT_I2S_DOUT") (pintype "bidirectional"))
    )
    (net (code "21") (name "I2S_MCLK") (class "Default")
      (node (ref "MCLK") (pin "1") (pinfunction "1_1") (pintype "passive"))
      (node (ref "U$1") (pin "I2S_MCLK") (pinfunction "I2S_MCLK_I2S_MCLK") (pintype "bidirectional"))
    )
    (net (code "22") (name "LOUT+") (class "Default")
      (node (ref "U$1") (pin "LOUT+") (pinfunction "LOUT+_LOUT+") (pintype "bidirectional"))
      (node (ref "U$2") (pin "LIN+") (pinfunction "LIN+_LIN+") (pintype "bidirectional"))
    )
    (net (code "23") (name "LOUT-") (class "Default")
      (node (ref "U$1") (pin "LOUT-") (pinfunction "LOUT-_LOUT-") (pintype "bidirectional"))
      (node (ref "U$2") (pin "LIN-") (pinfunction "LIN-_LIN-") (pintype "bidirectional"))
    )
    (net (code "24") (name "LRCLK") (class "Default")
      (node (ref "MEMS1") (pin "1") (pinfunction "WS_1") (pintype "input"))
      (node (ref "MEMS2") (pin "1") (pinfunction "WS_1") (pintype "input"))
      (node (ref "R7") (pin "1") (pinfunction "1_1") (pintype "passive"))
      (node (ref "U$1") (pin "I2S_LRCLK") (pinfunction "I2S_LRCLK_I2S_LRCLK") (pintype "bidirectional"))
    )
    (net (code "25") (name "MCLK") (class "Default")
      (node (ref "MCLK") (pin "2") (pinfunction "2_2") (pintype "passive"))
      (node (ref "U$3") (pin "11") (pinfunction "11/MOSI_11") (pintype "bidirectional"))
    )
    (net (code "26") (name "MISO") (class "Default")
      (node (ref "J7") (pin "7") (pinfunction "DAT0_7") (pintype "passive"))
      (node (ref "U$3") (pin "12") (pinfunction "12/MISO_12") (pintype "bidirectional"))
    )
    (net (code "27") (name "MOSI") (class "Default")
      (node (ref "J7") (pin "3") (pinfunction "CMD_3") (pintype "passive"))
      (node (ref "U$3") (pin "7") (pinfunction "7/RX3_7") (pintype "bidirectional"))
    )
    (net (code "28") (name "NEO_PIX1") (class "Default")
      (node (ref "LED1") (pin "4-DIN") (pinfunction "DI_4-DIN") (pintype "input"))
      (node (ref "U$3") (pin "5") (pinfunction "5/PWM_5") (pintype "bidirectional"))
    )
    (net (code "29") (name "NEO_PIX1_OUT") (class "Default")
      (node (ref "LED16") (pin "2-DOUT") (pinfunction "DO_2-DOUT") (pintype "output"))
      (node (ref "LED17") (pin "4-DIN") (pinfunction "DI_4-DIN") (pintype "input"))
    )
    (net (code "30") (name "Net-(FRONT_OUT-Pad1)") (class "Default")
      (node (ref "FRONT_OUT") (pin "1") (pinfunction "1_1") (pintype "passive"))
      (node (ref "U$2") (pin "LOUT+") (pinfunction "LOUT+_LOUT+") (pintype "bidirectional"))
    )
    (net (code "31") (name "Net-(FRONT_OUT-Pad2)") (class "Default")
      (node (ref "FRONT_OUT") (pin "2") (pinfunction "2_2") (pintype "passive"))
      (node (ref "U$2") (pin "LOUT-") (pinfunction "LOUT-_LOUT-") (pintype "bidirectional"))
    )
    (net (code "32") (name "Net-(LED1-DO)") (class "Default")
      (node (ref "LED1") (pin "2-DOUT") (pinfunction "DO_2-DOUT") (pintype "output"))
      (node (ref "LED2") (pin "4-DIN") (pinfunction "DI_4-DIN") (pintype "input"))
    )
    (net (code "33") (name "Net-(LED2-DO)") (class "Default")
      (node (ref "LED2") (pin "2-DOUT") (pinfunction "DO_2-DOUT") (pintype "output"))
      (node (ref "LED3") (pin "4-DIN") (pinfunction "DI_4-DIN") (pintype "input"))
    )
    (net (code "34") (name "Net-(LED3-DO)") (class "Default")
      (node (ref "LED3") (pin "2-DOUT") (pinfunction "DO_2-DOUT") (pintype "output"))
      (node (ref "LED4") (pin "4-DIN") (pinfunction "DI_4-DIN") (pintype "input"))
    )
    (net (code "35") (name "Net-(LED4-DO)") (class "Default")
      (node (ref "LED4") (pin "2-DOUT") (pinfunction "DO_2-DOUT") (pintype "output"))
      (node (ref "LED5") (pin "4-DIN") (pinfunction "DI_4-DIN") (pintype "input"))
    )
    (net (code "36") (name "Net-(LED5-DO)") (class "Default")
      (node (ref "LED5") (pin "2-DOUT") (pinfunction "DO_2-DOUT") (pintype "output"))
      (node (ref "LED6") (pin "4-DIN") (pinfunction "DI_4-DIN") (pintype "input"))
    )
    (net (code "37") (name "Net-(LED6-DO)") (class "Default")
      (node (ref "LED6") (pin "2-DOUT") (pinfunction "DO_2-DOUT") (pintype "output"))
      (node (ref "LED7") (pin "4-DIN") (pinfunction "DI_4-DIN") (pintype "input"))
    )
    (net (code "38") (name "Net-(LED7-DO)") (class "Default")
      (node (ref "LED7") (pin "2-DOUT") (pinfunction "DO_2-DOUT") (pintype "output"))
      (node (ref "LED8") (pin "4-DIN") (pinfunction "DI_4-DIN") (pintype "input"))
    )
    (net (code "39") (name "Net-(LED8-DO)") (class "Default")
      (node (ref "LED8") (pin "2-DOUT") (pinfunction "DO_2-DOUT") (pintype "output"))
      (node (ref "LED9") (pin "4-DIN") (pinfunction "DI_4-DIN") (pintype "input"))
    )
    (net (code "40") (name "Net-(LED10-DI)") (class "Default")
      (node (ref "LED10") (pin "4-DIN") (pinfunction "DI_4-DIN") (pintype "input"))
      (node (ref "LED9") (pin "2-DOUT") (pinfunction "DO_2-DOUT") (pintype "output"))
    )
    (net (code "41") (name "Net-(LED10-DO)") (class "Default")
      (node (ref "LED10") (pin "2-DOUT") (pinfunction "DO_2-DOUT") (pintype "output"))
      (node (ref "LED11") (pin "4-DIN") (pinfunction "DI_4-DIN") (pintype "input"))
    )
    (net (code "42") (name "Net-(LED11-DO)") (class "Default")
      (node (ref "LED11") (pin "2-DOUT") (pinfunction "DO_2-DOUT") (pintype "output"))
      (node (ref "LED12") (pin "4-DIN") (pinfunction "DI_4-DIN") (pintype "input"))
    )
    (net (code "43") (name "Net-(LED12-DO)") (class "Default")
      (node (ref "LED12") (pin "2-DOUT") (pinfunction "DO_2-DOUT") (pintype "output"))
      (node (ref "LED13") (pin "4-DIN") (pinfunction "DI_4-DIN") (pintype "input"))
    )
    (net (code "44") (name "Net-(LED13-DO)") (class "Default")
      (node (ref "LED13") (pin "2-DOUT") (pinfunction "DO_2-DOUT") (pintype "output"))
      (node (ref "LED14") (pin "4-DIN") (pinfunction "DI_4-DIN") (pintype "input"))
    )
    (net (code "45") (name "Net-(LED14-DO)") (class "Default")
      (node (ref "LED14") (pin "2-DOUT") (pinfunction "DO_2-DOUT") (pintype "output"))
      (node (ref "LED15") (pin "4-DIN") (pinfunction "DI_4-DIN") (pintype "input"))
    )
    (net (code "46") (name "Net-(LED15-DO)") (class "Default")
      (node (ref "LED15") (pin "2-DOUT") (pinfunction "DO_2-DOUT") (pintype "output"))
      (node (ref "LED16") (pin "4-DIN") (pinfunction "DI_4-DIN") (pintype "input"))
    )
    (net (code "47") (name "Net-(LED17-DO)") (class "Default")
      (node (ref "LED17") (pin "2-DOUT") (pinfunction "DO_2-DOUT") (pintype "output"))
      (node (ref "LED18") (pin "4-DIN") (pinfunction "DI_4-DIN") (pintype "input"))
    )
    (net (code "48") (name "Net-(LED18-DO)") (class "Default")
      (node (ref "LED18") (pin "2-DOUT") (pinfunction "DO_2-DOUT") (pintype "output"))
      (node (ref "LED19") (pin "4-DIN") (pinfunction "DI_4-DIN") (pintype "input"))
    )
    (net (code "49") (name "Net-(LED19-DO)") (class "Default")
      (node (ref "LED19") (pin "2-DOUT") (pinfunction "DO_2-DOUT") (pintype "output"))
      (node (ref "LED20") (pin "4-DIN") (pinfunction "DI_4-DIN") (pintype "input"))
    )
    (net (code "50") (name "Net-(MEMS1-DATA_OUT)") (class "Default")
      (node (ref "MEMS1") (pin "6") (pinfunction "DATA_OUT_6") (pintype "output"))
      (node (ref "R2") (pin "1") (pinfunction "1_1") (pintype "passive"))
    )
    (net (code "51") (name "Net-(MEMS2-DATA_OUT)") (class "Default")
      (node (ref "MEMS2") (pin "6") (pinfunction "DATA_OUT_6") (pintype "output"))
      (node (ref "R9") (pin "1") (pinfunction "1_1") (pintype "passive"))
    )
    (net (code "52") (name "Net-(REAR_OUT-Pad1)") (class "Default")
      (node (ref "REAR_OUT") (pin "1") (pinfunction "1_1") (pintype "passive"))
      (node (ref "U$2") (pin "ROUT+") (pinfunction "ROUT+_ROUT+") (pintype "bidirectional"))
    )
    (net (code "53") (name "Net-(REAR_OUT-Pad2)") (class "Default")
      (node (ref "REAR_OUT") (pin "2") (pinfunction "2_2") (pintype "passive"))
      (node (ref "U$2") (pin "ROUT-") (pinfunction "ROUT-_ROUT-") (pintype "bidirectional"))
    )
    (net (code "54") (name "Net-(U$5-PadP$10)") (class "Default")
      (node (ref "U$5") (pin "P$10") (pinfunction "P$10_P$10") (pintype "bidirectional"))
      (node (ref "U$5") (pin "P$11") (pinfunction "P$11_P$11") (pintype "bidirectional"))
      (node (ref "U$5") (pin "P$12") (pinfunction "P$12_P$12") (pintype "bidirectional"))
      (node (ref "U$5") (pin "P$4") (pinfunction "P$4_P$4") (pintype "bidirectional"))
      (node (ref "U$5") (pin "P$5") (pinfunction "P$5_P$5") (pintype "bidirectional"))
      (node (ref "U$5") (pin "P$6") (pinfunction "P$6_P$6") (pintype "bidirectional"))
    )
    (net (code "55") (name "Net-(U3-*PB)") (class "Default")
      (node (ref "C36") (pin "1") (pinfunction "1_1") (pintype "passive"))
      (node (ref "R10") (pin "1") (pinfunction "1_1") (pintype "passive"))
      (node (ref "U3") (pin "2") (pinfunction "*PB_2") (pintype "input"))
    )
    (net (code "56") (name "Net-(VMEL1-VDD)") (class "Default")
      (node (ref "C10") (pin "1") (pinfunction "1_1") (pintype "passive"))
      (node (ref "C8") (pin "1") (pinfunction "1_1") (pintype "passive"))
      (node (ref "R1") (pin "1") (pinfunction "1_1") (pintype "passive"))
      (node (ref "VMEL1") (pin "6") (pinfunction "VDD_6") (pintype "power_in"))
    )
    (net (code "57") (name "Net-(VMEL2-VDD)") (class "Default")
      (node (ref "C42") (pin "1") (pinfunction "1_1") (pintype "passive"))
      (node (ref "C43") (pin "1") (pinfunction "1_1") (pintype "passive"))
      (node (ref "R6") (pin "1") (pinfunction "1_1") (pintype "passive"))
      (node (ref "VMEL2") (pin "6") (pinfunction "VDD_6") (pintype "power_in"))
    )
    (net (code "58") (name "ONT") (class "Default")
      (node (ref "C37") (pin "1") (pinfunction "1_1") (pintype "passive"))
      (node (ref "U3") (pin "3") (pinfunction "ONT_3") (pintype "input"))
    )
    (net (code "59") (name "PDT") (class "Default")
      (node (ref "C2") (pin "1") (pinfunction "1_1") (pintype "passive"))
      (node (ref "U3") (pin "7") (pinfunction "PDT_7") (pintype "input"))
    )
    (net (code "60") (name "POT1") (class "Default")
      (node (ref "U$3") (pin "17/A3") (pinfunction "17/A3/T_17/A3") (pintype "bidirectional"))
      (node (ref "U$4") (pin "P$1") (pinfunction "P$1_P$1") (pintype "bidirectional"))
    )
    (net (code "61") (name "POT2") (class "Default")
      (node (ref "U$3") (pin "21/A7") (pinfunction "21/A7/PWM_21/A7") (pintype "bidirectional"))
      (node (ref "U$6") (pin "P$1") (pinfunction "P$1_P$1") (pintype "bidirectional"))
    )
    (net (code "62") (name "PWR_INT") (class "Default")
      (node (ref "R8") (pin "1") (pinfunction "1_1") (pintype "passive"))
      (node (ref "U$3") (pin "2") (pinfunction "2_2") (pintype "bidirectional"))
      (node (ref "U3") (pin "5") (pinfunction "*INT_5") (pintype "output"))
    )
    (net (code "63") (name "PWR_KILL") (class "Default")
      (node (ref "U$3") (pin "3") (pinfunction "3/CAN-TX/PWM_3") (pintype "bidirectional"))
      (node (ref "U3") (pin "8") (pinfunction "*KILL_8") (pintype "input"))
    )
    (net (code "64") (name "ROUT+") (class "Default")
      (node (ref "U$1") (pin "ROUT+") (pinfunction "ROUT+_ROUT+") (pintype "bidirectional"))
      (node (ref "U$2") (pin "RIN+") (pinfunction "RIN+_RIN+") (pintype "bidirectional"))
    )
    (net (code "65") (name "ROUT-") (class "Default")
      (node (ref "U$1") (pin "ROUT-") (pinfunction "ROUT-_ROUT-") (pintype "bidirectional"))
      (node (ref "U$2") (pin "RIN-") (pinfunction "RIN-_RIN-") (pintype "bidirectional"))
    )
    (net (code "66") (name "SCL") (class "Default")
      (node (ref "R4") (pin "1") (pinfunction "1_1") (pintype "passive"))
      (node (ref "U$1") (pin "SCL") (pinfunction "SCL_SCL") (pintype "bidirectional"))
      (node (ref "U$3") (pin "19/A5") (pinfunction "19/A5/T/SCL0_19/A5") (pintype "bidirectional"))
      (node (ref "U2") (pin "2") (pinfunction "SCL_2") (pintype "bidirectional"))
      (node (ref "VMEL1") (pin "5") (pinfunction "SCL_5") (pintype "input"))
      (node (ref "VMEL2") (pin "5") (pinfunction "SCL_5") (pintype "input"))
    )
    (net (code "67") (name "SDA") (class "Default")
      (node (ref "R3") (pin "1") (pinfunction "1_1") (pintype "passive"))
      (node (ref "U$1") (pin "SDA") (pinfunction "SDA_SDA") (pintype "bidirectional"))
      (node (ref "U$3") (pin "18/A4") (pinfunction "18/A4/T/SDA0_18/A4") (pintype "bidirectional"))
      (node (ref "U2") (pin "3") (pinfunction "SDA_3") (pintype "bidirectional"))
      (node (ref "VMEL1") (pin "2") (pinfunction "SDA_2") (pintype "bidirectional"))
      (node (ref "VMEL2") (pin "2") (pinfunction "SDA_2") (pintype "bidirectional"))
    )
    (net (code "68") (name "SD_CS") (class "Default")
      (node (ref "J7") (pin "2") (pinfunction "CD/DAT3_2") (pintype "passive"))
      (node (ref "R11") (pin "1") (pinfunction "1_1") (pintype "passive"))
      (node (ref "U$3") (pin "10") (pinfunction "10/TX2/PWM_10") (pintype "bidirectional"))
    )
    (net (code "69") (name "SPI_CLK") (class "Default")
      (node (ref "J7") (pin "5") (pinfunction "CLK_5") (pintype "passive"))
      (node (ref "U$3") (pin "14/A0") (pinfunction "14/A1_14/A0") (pintype "bidirectional"))
    )
    (net (code "70") (name "VEML_INT_1") (class "Default")
      (node (ref "VMEL1") (pin "3") (pinfunction "INT_3") (pintype "output"))
    )
    (net (code "71") (name "VEML_INT_2") (class "Default")
      (node (ref "VMEL2") (pin "3") (pinfunction "INT_3") (pintype "output"))
    )
    (net (code "72") (name "_BCLK") (class "Default")
      (node (ref "R5") (pin "2") (pinfunction "2_2") (pintype "passive"))
      (node (ref "U$3") (pin "9") (pinfunction "9/RX2/PWM_9") (pintype "bidirectional"))
    )
    (net (code "73") (name "_BUT1") (class "Default")
      (node (ref "DIN1") (pin "2") (pinfunction "2_2") (pintype "passive"))
      (node (ref "SW1") (pin "12") (pinfunction "12_12") (pintype "passive"))
    )
    (net (code "74") (name "_BUT2") (class "Default")
      (node (ref "DIN2") (pin "2") (pinfunction "2_2") (pintype "passive"))
      (node (ref "SW1") (pin "11") (pinfunction "11_11") (pintype "passive"))
    )
    (net (code "75") (name "_LRCLK") (class "Default")
      (node (ref "R7") (pin "2") (pinfunction "2_2") (pintype "passive"))
      (node (ref "U$3") (pin "23/A9") (pinfunction "23/A9/T/PWM_23/A9") (pintype "bidirectional"))
    )
    (net (code "76") (name "unconnected-(J7-CD_SW-Pad9)") (class "Default")
      (node (ref "J7") (pin "9") (pinfunction "CD_SW_9") (pintype "passive"))
    )
    (net (code "77") (name "unconnected-(J7-DAT1-Pad8)") (class "Default")
      (node (ref "J7") (pin "8") (pinfunction "DAT1_8") (pintype "passive"))
    )
    (net (code "78") (name "unconnected-(J7-DAT2-Pad1)") (class "Default")
      (node (ref "J7") (pin "1") (pinfunction "DAT2_1") (pintype "passive"))
    )
    (net (code "79") (name "unconnected-(LED20-DO-Pad2-DOUT)") (class "Default")
      (node (ref "LED20") (pin "2-DOUT") (pinfunction "DO_2-DOUT") (pintype "output"))
    )
    (net (code "80") (name "unconnected-(U$1-PadNA1)") (class "Default")
      (node (ref "U$1") (pin "NA1") (pinfunction "NA1_NA1") (pintype "bidirectional"))
    )
    (net (code "81") (name "unconnected-(U$1-PadNA2)") (class "Default")
      (node (ref "U$1") (pin "NA2") (pinfunction "NA2_NA2") (pintype "bidirectional"))
    )
  )
)
